# Gas_Sampler-NOAA_Conn.net
KiCad netlist of a schematic drawn in Altium Designer
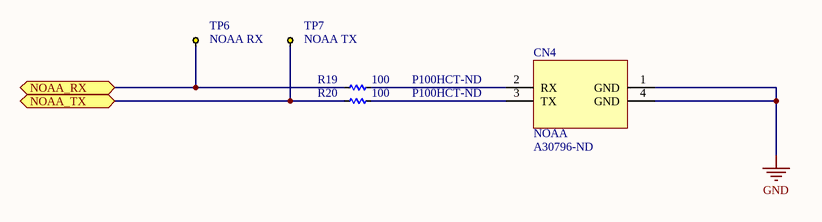
[diagram p0: Gas_Sampler-NOAA_Conn.SchDoc]

(export (version "E")
  (design (tool "Eeschema 10.0.6"))
  (components
    (comp (ref "CN4")
      (value "NOAA")
      (footprint "TE_3-641216-4")
      (description "CONN HEADER VERT 4POS 2.54MM")
      (fields
        (field (name "MANUFACTURER") "TE Connectivity AMP Connectors")
        (field (name "MANUFACTURER PART NUMBER") "3-641216-4")
        (field (name "SUPPLIER PART NUMBER 1") "A30796-ND")
      )
      (libsource (lib "connector") (part "CONN_NOAA_XDATA_RA_3-641216-4"))
    )
    (comp (ref "R19")
      (value "100")
      (footprint "R0603")
      (description "RES 100 OHM 1/10W 1% 0603 SMD")
      (fields
        (field (name "MANUFACTURER") "Panasonic Electronic Components")
        (field (name "MANUFACTURER PART NUMBER") "ERJ-3EKF1000V")
        (field (name "SUPPLIER PART NUMBER 1") "P100HCT-ND")
      )
      (libsource (lib "resistor") (part "RES_0603_100_OHM_1/10W_1%"))
    )
    (comp (ref "R20")
      (value "100")
      (footprint "R0603")
      (description "RES 100 OHM 1/10W 1% 0603 SMD")
      (fields
        (field (name "MANUFACTURER") "Panasonic Electronic Components")
        (field (name "MANUFACTURER PART NUMBER") "ERJ-3EKF1000V")
        (field (name "SUPPLIER PART NUMBER 1") "P100HCT-ND")
      )
      (libsource (lib "resistor") (part "RES_0603_100_OHM_1/10W_1%"))
    )
    (comp (ref "TP6")
      (value "NOAA RX")
      (footprint "TP_KEYSTONE_5001")
      (description "PC TEST POINT TH RING")
      (fields
        (field (name "MANUFACTURER") "Keystone Electronics")
        (field (name "MANUFACTURER PART NUMBER") "5001")
      )
      (libsource (lib "miscellaneous") (part "TEST_KEYSTONE5001"))
    )
    (comp (ref "TP7")
      (value "NOAA TX")
      (footprint "TP_KEYSTONE_5001")
      (description "PC TEST POINT TH RING")
      (fields
        (field (name "MANUFACTURER") "Keystone Electronics")
        (field (name "MANUFACTURER PART NUMBER") "5001")
      )
      (libsource (lib "miscellaneous") (part "TEST_KEYSTONE5001"))
    )
  )
  (nets
    (net (code "1") (name "/NOAA_RX") (class "Default")
      (node (ref "R19") (pin "1") (pintype "passive"))
      (node (ref "TP6") (pin "1") (pintype "passive"))
    )
    (net (code "2") (name "/NOAA_TX") (class "Default")
      (node (ref "R20") (pin "1") (pintype "passive"))
      (node (ref "TP7") (pin "1") (pintype "passive"))
    )
    (net (code "3") (name "GND") (class "Default")
      (node (ref "CN4") (pin "1") (pinfunction "GND_1") (pintype "passive"))
      (node (ref "CN4") (pin "4") (pinfunction "GND_4") (pintype "passive"))
    )
    (net (code "4") (name "Net-(CN4-RX)") (class "Default")
      (node (ref "CN4") (pin "2") (pinfunction "RX_2") (pintype "passive"))
      (node (ref "R19") (pin "2") (pintype "passive"))
    )
    (net (code "5") (name "Net-(CN4-TX)") (class "Default")
      (node (ref "CN4") (pin "3") (pinfunction "TX_3") (pintype "passive"))
      (node (ref "R20") (pin "2") (pintype "passive"))
    )
  )
)
